# Project_Canary_V4_6.net
KiCad netlist of a schematic drawn in EAGLE
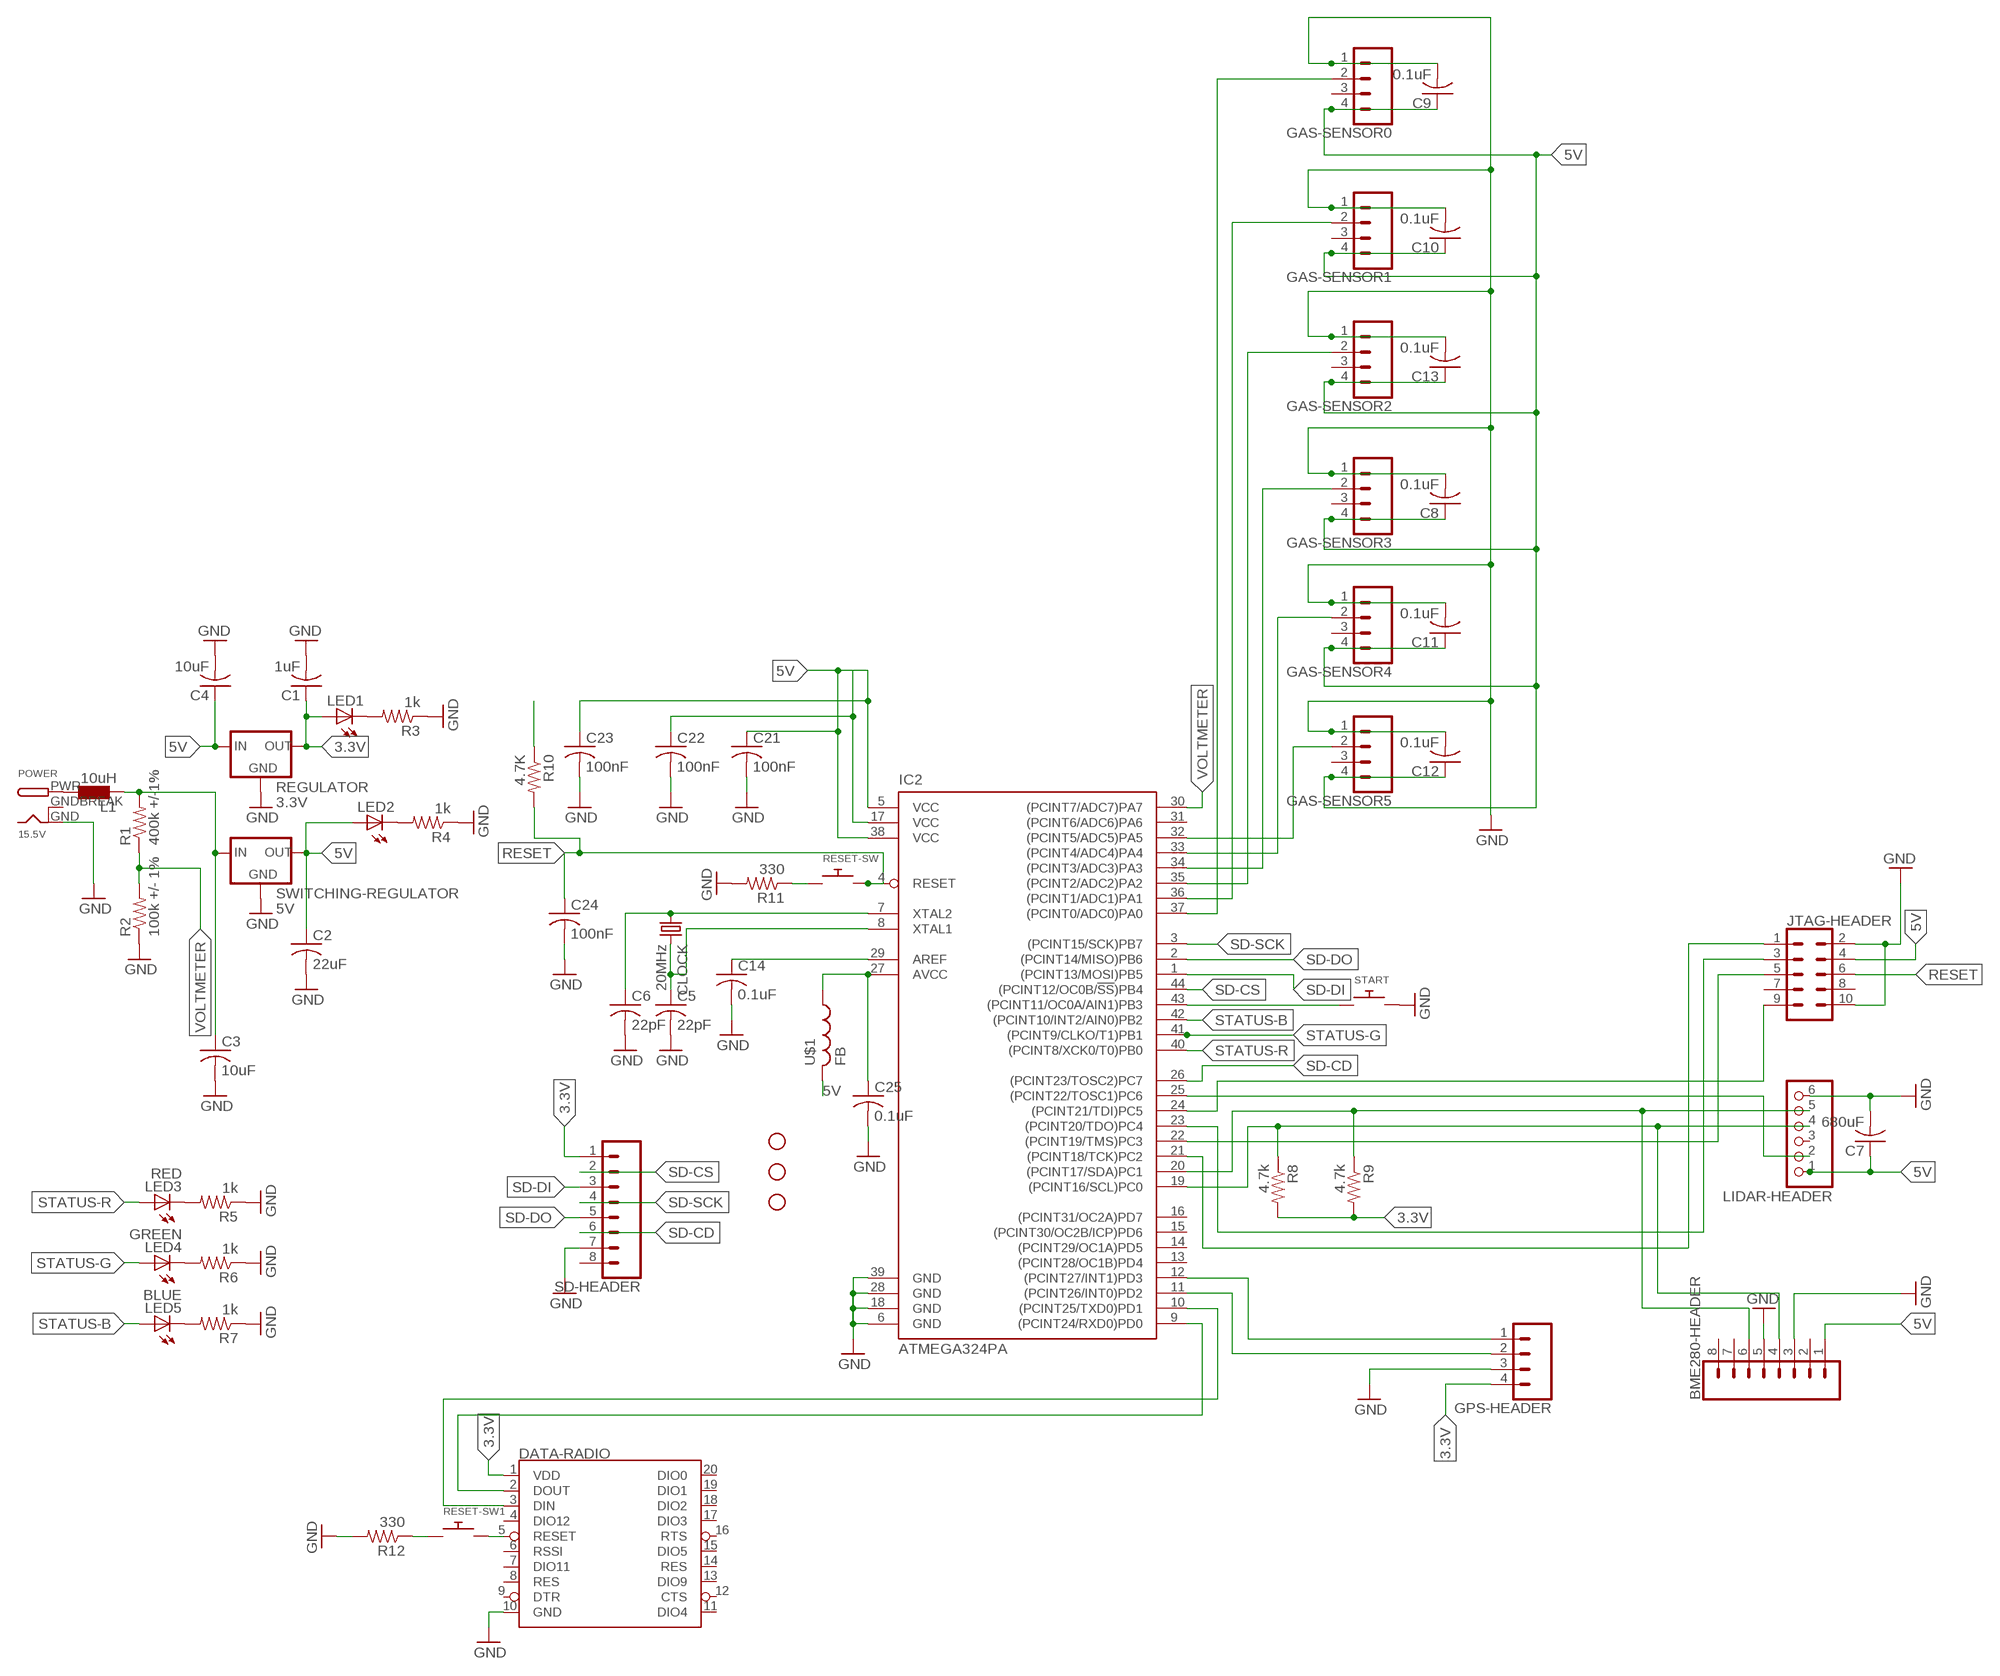
[diagram p0: schematic, sheet 1]

(export (version "E")
  (design (tool "Eeschema 10.0.6"))
  (components
    (comp (ref "BME280-HEADER")
      (value "CONN_08\"")
      (footprint "eagle-import:1X08")
      (libsource (lib "eagle-import") (part "CONN_08{dblquote}"))
    )
    (comp (ref "C1")
      (value "1uF")
      (footprint "eagle-import:C0805")
      (libsource (lib "eagle-import") (part "C-USC0805"))
    )
    (comp (ref "C2")
      (value "22uF")
      (footprint "eagle-import:C0603")
      (libsource (lib "eagle-import") (part "C-USC0603"))
    )
    (comp (ref "C3")
      (value "10uF")
      (footprint "eagle-import:C0805")
      (libsource (lib "eagle-import") (part "C-USC0805"))
    )
    (comp (ref "C4")
      (value "10uF")
      (footprint "eagle-import:C0603")
      (libsource (lib "eagle-import") (part "C-USC0603"))
    )
    (comp (ref "C5")
      (value "22pF")
      (footprint "eagle-import:C0603")
      (libsource (lib "eagle-import") (part "C-USC0603"))
    )
    (comp (ref "C6")
      (value "22pF")
      (footprint "eagle-import:C0603")
      (libsource (lib "eagle-import") (part "C-USC0603"))
    )
    (comp (ref "C7")
      (value "680uF")
      (footprint "eagle-import:C0603")
      (libsource (lib "eagle-import") (part "C-USC0603"))
    )
    (comp (ref "C8")
      (value "0.1uF")
      (footprint "eagle-import:C0603")
      (libsource (lib "eagle-import") (part "C-USC0603"))
    )
    (comp (ref "C9")
      (value "0.1uF")
      (footprint "eagle-import:C0603")
      (libsource (lib "eagle-import") (part "C-USC0603"))
    )
    (comp (ref "C10")
      (value "0.1uF")
      (footprint "eagle-import:C0603")
      (libsource (lib "eagle-import") (part "C-USC0603"))
    )
    (comp (ref "C11")
      (value "0.1uF")
      (footprint "eagle-import:C0603")
      (libsource (lib "eagle-import") (part "C-USC0603"))
    )
    (comp (ref "C12")
      (value "0.1uF")
      (footprint "eagle-import:C0603")
      (libsource (lib "eagle-import") (part "C-USC0603"))
    )
    (comp (ref "C13")
      (value "0.1uF")
      (footprint "eagle-import:C0603")
      (libsource (lib "eagle-import") (part "C-USC0603"))
    )
    (comp (ref "C14")
      (value "0.1uF")
      (footprint "eagle-import:C0603")
      (libsource (lib "eagle-import") (part "C-USC0603"))
    )
    (comp (ref "C21")
      (value "100nF")
      (footprint "eagle-import:C0603")
      (libsource (lib "eagle-import") (part "C-USC0603"))
    )
    (comp (ref "C22")
      (value "100nF")
      (footprint "eagle-import:C0603")
      (libsource (lib "eagle-import") (part "C-USC0603"))
    )
    (comp (ref "C23")
      (value "100nF")
      (footprint "eagle-import:C0603")
      (libsource (lib "eagle-import") (part "C-USC0603"))
    )
    (comp (ref "C24")
      (value "100nF")
      (footprint "eagle-import:C0805")
      (libsource (lib "eagle-import") (part "C-USC0805"))
    )
    (comp (ref "C25")
      (value "0.1uF")
      (footprint "eagle-import:C0603")
      (libsource (lib "eagle-import") (part "C-USC0603"))
    )
    (comp (ref "CLOCK")
      (value "20MHz")
      (footprint "eagle-import:86SMX")
      (libsource (lib "eagle-import") (part "CRYSTAL68SMX"))
    )
    (comp (ref "DATA-RADIO")
      (value "XBEE")
      (footprint "eagle-import:XBEE")
      (libsource (lib "eagle-import") (part "XBEE"))
    )
    (comp (ref "GAS-SENSOR0")
      (value "CONN_04")
      (footprint "eagle-import:1X04")
      (libsource (lib "eagle-import") (part "CONN_04"))
    )
    (comp (ref "GAS-SENSOR1")
      (value "CONN_04")
      (footprint "eagle-import:1X04")
      (libsource (lib "eagle-import") (part "CONN_04"))
    )
    (comp (ref "GAS-SENSOR2")
      (value "CONN_04")
      (footprint "eagle-import:1X04")
      (libsource (lib "eagle-import") (part "CONN_04"))
    )
    (comp (ref "GAS-SENSOR3")
      (value "CONN_04")
      (footprint "eagle-import:1X04")
      (libsource (lib "eagle-import") (part "CONN_04"))
    )
    (comp (ref "GAS-SENSOR4")
      (value "CONN_04")
      (footprint "eagle-import:1X04")
      (libsource (lib "eagle-import") (part "CONN_04"))
    )
    (comp (ref "GAS-SENSOR5")
      (value "CONN_04")
      (footprint "eagle-import:1X04")
      (libsource (lib "eagle-import") (part "CONN_04"))
    )
    (comp (ref "GPS-HEADER")
      (value "CONN_04")
      (footprint "eagle-import:1X04")
      (libsource (lib "eagle-import") (part "CONN_04"))
    )
    (comp (ref "IC2")
      (value "ATMEGA324PA")
      (footprint "eagle-import:TQFP44")
      (fields (field (name "MPN") "ATMEGA644PV-10AU"))
      (libsource (lib "eagle-import") (part "ATMEGA644A"))
    )
    (comp (ref "JTAG-HEADER")
      (value "CONN_05X2PTH")
      (footprint "eagle-import:2X5")
      (libsource (lib "eagle-import") (part "CONN_05X2PTH"))
    )
    (comp (ref "L1")
      (value "10uH")
      (footprint "eagle-import:L1812")
      (libsource (lib "eagle-import") (part "L"))
    )
    (comp (ref "LED1")
      (value "LEDCHIP-LED0805")
      (footprint "eagle-import:CHIP-LED0805")
      (libsource (lib "eagle-import") (part "LEDCHIP-LED0805"))
    )
    (comp (ref "LED2")
      (value "LEDCHIP-LED0805")
      (footprint "eagle-import:CHIP-LED0805")
      (libsource (lib "eagle-import") (part "LEDCHIP-LED0805"))
    )
    (comp (ref "LED3")
      (value "RED")
      (footprint "eagle-import:CHIP-LED0805")
      (libsource (lib "eagle-import") (part "LEDCHIP-LED0805"))
    )
    (comp (ref "LED4")
      (value "GREEN")
      (footprint "eagle-import:CHIP-LED0805")
      (libsource (lib "eagle-import") (part "LEDCHIP-LED0805"))
    )
    (comp (ref "LED5")
      (value "BLUE")
      (footprint "eagle-import:CHIP-LED0805")
      (libsource (lib "eagle-import") (part "LEDCHIP-LED0805"))
    )
    (comp (ref "LIDAR-HEADER")
      (value "PINHD-1X6")
      (footprint "eagle-import:1X06")
      (libsource (lib "eagle-import") (part "PINHD-1X6"))
    )
    (comp (ref "MOUNT-HOLE1")
      (value "STAND-OFF")
      (footprint "eagle-import:STAND-OFF")
      (libsource (lib "eagle-import") (part "STAND-OFF"))
    )
    (comp (ref "MOUNT-HOLE2")
      (value "STAND-OFF")
      (footprint "eagle-import:STAND-OFF")
      (libsource (lib "eagle-import") (part "STAND-OFF"))
    )
    (comp (ref "MOUNT-HOLE3")
      (value "STAND-OFF")
      (footprint "eagle-import:STAND-OFF")
      (libsource (lib "eagle-import") (part "STAND-OFF"))
    )
    (comp (ref "POWER")
      (value "15.5V")
      (footprint "eagle-import:DCJACK_2MM_PTH")
      (libsource (lib "eagle-import") (part "DCBARRELPTH"))
    )
    (comp (ref "R1")
      (value "400k +/-1%")
      (footprint "eagle-import:M0805")
      (libsource (lib "eagle-import") (part "R-US_M0805"))
    )
    (comp (ref "R2")
      (value "100k +/- 1%")
      (footprint "eagle-import:M0805")
      (libsource (lib "eagle-import") (part "R-US_M0805"))
    )
    (comp (ref "R3")
      (value "1k")
      (footprint "eagle-import:M0805")
      (libsource (lib "eagle-import") (part "R-US_M0805"))
    )
    (comp (ref "R4")
      (value "1k")
      (footprint "eagle-import:M0805")
      (libsource (lib "eagle-import") (part "R-US_M0805"))
    )
    (comp (ref "R5")
      (value "1k")
      (footprint "eagle-import:M0805")
      (libsource (lib "eagle-import") (part "R-US_M0805"))
    )
    (comp (ref "R6")
      (value "1k")
      (footprint "eagle-import:M0805")
      (libsource (lib "eagle-import") (part "R-US_M0805"))
    )
    (comp (ref "R7")
      (value "1k")
      (footprint "eagle-import:M0805")
      (libsource (lib "eagle-import") (part "R-US_M0805"))
    )
    (comp (ref "R8")
      (value "4.7k")
      (footprint "eagle-import:M0805")
      (libsource (lib "eagle-import") (part "R-US_M0805"))
    )
    (comp (ref "R9")
      (value "4.7k")
      (footprint "eagle-import:M0805")
      (libsource (lib "eagle-import") (part "R-US_M0805"))
    )
    (comp (ref "R10")
      (value "4.7K")
      (footprint "eagle-import:M0805")
      (libsource (lib "eagle-import") (part "R-US_M0805"))
    )
    (comp (ref "R11")
      (value "330")
      (footprint "eagle-import:M0805")
      (libsource (lib "eagle-import") (part "R-US_M0805"))
    )
    (comp (ref "R12")
      (value "330")
      (footprint "eagle-import:M0805")
      (libsource (lib "eagle-import") (part "R-US_M0805"))
    )
    (comp (ref "REGULATOR")
      (value "3.3V")
      (footprint "eagle-import:TO220-IGO")
      (libsource (lib "eagle-import") (part "V_REG_78XXSINK"))
    )
    (comp (ref "RESET-SW")
      (value "SWITCH_PUSHBUTTONSOFTTOUCHSMD_SJ")
      (footprint "eagle-import:PUSHBUTTON_SMD_SJ")
      (libsource (lib "eagle-import") (part "SWITCH_PUSHBUTTONSOFTTOUCHSMD_SJ"))
    )
    (comp (ref "RESET-SW1")
      (value "SWITCH_PUSHBUTTONSOFTTOUCHSMD_SJ")
      (footprint "eagle-import:PUSHBUTTON_SMD_SJ")
      (libsource (lib "eagle-import") (part "SWITCH_PUSHBUTTONSOFTTOUCHSMD_SJ"))
    )
    (comp (ref "SD-HEADER")
      (value "CONN_08\"")
      (footprint "eagle-import:1X08")
      (libsource (lib "eagle-import") (part "CONN_08{dblquote}"))
    )
    (comp (ref "START")
      (value "SWITCH_PUSHBUTTONSOFTTOUCHSMD_SJ")
      (footprint "eagle-import:PUSHBUTTON_SMD_SJ")
      (libsource (lib "eagle-import") (part "SWITCH_PUSHBUTTONSOFTTOUCHSMD_SJ"))
    )
    (comp (ref "SWITCHING-REGULATOR")
      (value "5V")
      (footprint "eagle-import:TO220-IGO")
      (libsource (lib "eagle-import") (part "V_REG_78XXSINK"))
    )
    (comp (ref "U$1") (value "FB") (footprint "eagle-import:FB") (libsource (lib "eagle-import") (part "FB")))
  )
  (nets
    (net (code "1") (name "/GNDBREAK") (class "Default")
      (node (ref "POWER") (pin "GNDBREAK") (pinfunction "GNDBREAK_GNDBREAK") (pintype "power_in"))
    )
    (net (code "2") (name "3.3V") (class "Default")
      (node (ref "C1") (pin "1") (pinfunction "1_1") (pintype "passive"))
      (node (ref "DATA-RADIO") (pin "1") (pinfunction "VDD_1") (pintype "power_in"))
      (node (ref "GPS-HEADER") (pin "4") (pinfunction "4_4") (pintype "passive"))
      (node (ref "LED1") (pin "A") (pinfunction "A_A") (pintype "passive"))
      (node (ref "R8") (pin "2") (pinfunction "2_2") (pintype "passive"))
      (node (ref "R9") (pin "2") (pinfunction "2_2") (pintype "passive"))
      (node (ref "REGULATOR") (pin "OUT") (pinfunction "OUT_OUT") (pintype "passive"))
      (node (ref "SD-HEADER") (pin "1") (pinfunction "1_1") (pintype "passive"))
    )
    (net (code "3") (name "5V") (class "Default")
      (node (ref "BME280-HEADER") (pin "1") (pinfunction "1_1") (pintype "passive"))
      (node (ref "C10") (pin "1") (pinfunction "1_1") (pintype "passive"))
      (node (ref "C11") (pin "1") (pinfunction "1_1") (pintype "passive"))
      (node (ref "C12") (pin "1") (pinfunction "1_1") (pintype "passive"))
      (node (ref "C13") (pin "1") (pinfunction "1_1") (pintype "passive"))
      (node (ref "C2") (pin "1") (pinfunction "1_1") (pintype "passive"))
      (node (ref "C21") (pin "1") (pinfunction "1_1") (pintype "passive"))
      (node (ref "C22") (pin "1") (pinfunction "1_1") (pintype "passive"))
      (node (ref "C23") (pin "1") (pinfunction "1_1") (pintype "passive"))
      (node (ref "C4") (pin "1") (pinfunction "1_1") (pintype "passive"))
      (node (ref "C7") (pin "1") (pinfunction "1_1") (pintype "passive"))
      (node (ref "C8") (pin "1") (pinfunction "1_1") (pintype "passive"))
      (node (ref "C9") (pin "1") (pinfunction "1_1") (pintype "passive"))
      (node (ref "GAS-SENSOR0") (pin "4") (pinfunction "4_4") (pintype "passive"))
      (node (ref "GAS-SENSOR1") (pin "4") (pinfunction "4_4") (pintype "passive"))
      (node (ref "GAS-SENSOR2") (pin "4") (pinfunction "4_4") (pintype "passive"))
      (node (ref "GAS-SENSOR3") (pin "4") (pinfunction "4_4") (pintype "passive"))
      (node (ref "GAS-SENSOR4") (pin "4") (pinfunction "4_4") (pintype "passive"))
      (node (ref "GAS-SENSOR5") (pin "4") (pinfunction "4_4") (pintype "passive"))
      (node (ref "IC2") (pin "17") (pinfunction "VCC_17") (pintype "power_in"))
      (node (ref "IC2") (pin "38") (pinfunction "VCC_38") (pintype "power_in"))
      (node (ref "IC2") (pin "5") (pinfunction "VCC_5") (pintype "power_in"))
      (node (ref "JTAG-HEADER") (pin "4") (pinfunction "4_4") (pintype "passive"))
      (node (ref "LED2") (pin "A") (pinfunction "A_A") (pintype "passive"))
      (node (ref "LIDAR-HEADER") (pin "1") (pinfunction "1_1") (pintype "passive"))
      (node (ref "REGULATOR") (pin "IN") (pinfunction "IN_IN") (pintype "input"))
      (node (ref "SWITCHING-REGULATOR") (pin "OUT") (pinfunction "OUT_OUT") (pintype "passive"))
      (node (ref "U$1") (pin "P$2") (pinfunction "2_P$2") (pintype "passive"))
    )
    (net (code "4") (name "GND") (class "Default")
      (node (ref "BME280-HEADER") (pin "3") (pinfunction "3_3") (pintype "passive"))
      (node (ref "BME280-HEADER") (pin "5") (pinfunction "5_5") (pintype "passive"))
      (node (ref "C1") (pin "2") (pinfunction "2_2") (pintype "passive"))
      (node (ref "C10") (pin "2") (pinfunction "2_2") (pintype "passive"))
      (node (ref "C11") (pin "2") (pinfunction "2_2") (pintype "passive"))
      (node (ref "C12") (pin "2") (pinfunction "2_2") (pintype "passive"))
      (node (ref "C13") (pin "2") (pinfunction "2_2") (pintype "passive"))
      (node (ref "C14") (pin "2") (pinfunction "2_2") (pintype "passive"))
      (node (ref "C2") (pin "2") (pinfunction "2_2") (pintype "passive"))
      (node (ref "C21") (pin "2") (pinfunction "2_2") (pintype "passive"))
      (node (ref "C22") (pin "2") (pinfunction "2_2") (pintype "passive"))
      (node (ref "C23") (pin "2") (pinfunction "2_2") (pintype "passive"))
      (node (ref "C24") (pin "2") (pinfunction "2_2") (pintype "passive"))
      (node (ref "C25") (pin "2") (pinfunction "2_2") (pintype "passive"))
      (node (ref "C3") (pin "2") (pinfunction "2_2") (pintype "passive"))
      (node (ref "C4") (pin "2") (pinfunction "2_2") (pintype "passive"))
      (node (ref "C5") (pin "2") (pinfunction "2_2") (pintype "passive"))
      (node (ref "C6") (pin "2") (pinfunction "2_2") (pintype "passive"))
      (node (ref "C7") (pin "2") (pinfunction "2_2") (pintype "passive"))
      (node (ref "C8") (pin "2") (pinfunction "2_2") (pintype "passive"))
      (node (ref "C9") (pin "2") (pinfunction "2_2") (pintype "passive"))
      (node (ref "DATA-RADIO") (pin "10") (pinfunction "GND_10") (pintype "power_in"))
      (node (ref "GAS-SENSOR0") (pin "1") (pinfunction "1_1") (pintype "passive"))
      (node (ref "GAS-SENSOR1") (pin "1") (pinfunction "1_1") (pintype "passive"))
      (node (ref "GAS-SENSOR2") (pin "1") (pinfunction "1_1") (pintype "passive"))
      (node (ref "GAS-SENSOR3") (pin "1") (pinfunction "1_1") (pintype "passive"))
      (node (ref "GAS-SENSOR4") (pin "1") (pinfunction "1_1") (pintype "passive"))
      (node (ref "GAS-SENSOR5") (pin "1") (pinfunction "1_1") (pintype "passive"))
      (node (ref "GPS-HEADER") (pin "3") (pinfunction "3_3") (pintype "passive"))
      (node (ref "IC2") (pin "18") (pinfunction "GND_18") (pintype "power_in"))
      (node (ref "IC2") (pin "28") (pinfunction "GND_28") (pintype "power_in"))
      (node (ref "IC2") (pin "39") (pinfunction "GND_39") (pintype "power_in"))
      (node (ref "IC2") (pin "6") (pinfunction "GND_6") (pintype "power_in"))
      (node (ref "JTAG-HEADER") (pin "10") (pinfunction "10_10") (pintype "passive"))
      (node (ref "JTAG-HEADER") (pin "2") (pinfunction "2_2") (pintype "passive"))
      (node (ref "LIDAR-HEADER") (pin "6") (pinfunction "6_6") (pintype "passive"))
      (node (ref "POWER") (pin "GND") (pinfunction "GND_GND") (pintype "power_in"))
      (node (ref "R11") (pin "2") (pinfunction "2_2") (pintype "passive"))
      (node (ref "R12") (pin "2") (pinfunction "2_2") (pintype "passive"))
      (node (ref "R2") (pin "1") (pinfunction "1_1") (pintype "passive"))
      (node (ref "R3") (pin "1") (pinfunction "1_1") (pintype "passive"))
      (node (ref "R4") (pin "1") (pinfunction "1_1") (pintype "passive"))
      (node (ref "R5") (pin "1") (pinfunction "1_1") (pintype "passive"))
      (node (ref "R6") (pin "1") (pinfunction "1_1") (pintype "passive"))
      (node (ref "R7") (pin "1") (pinfunction "1_1") (pintype "passive"))
      (node (ref "REGULATOR") (pin "GND") (pinfunction "GND_GND") (pintype "input"))
      (node (ref "SD-HEADER") (pin "7") (pinfunction "7_7") (pintype "passive"))
      (node (ref "START") (pin "P$2") (pinfunction "P$2_P$2") (pintype "passive"))
      (node (ref "SWITCHING-REGULATOR") (pin "GND") (pinfunction "GND_GND") (pintype "input"))
    )
    (net (code "5") (name "Net-(C3-Pad1)") (class "Default")
      (node (ref "C3") (pin "1") (pinfunction "1_1") (pintype "passive"))
      (node (ref "L1") (pin "2") (pinfunction "2_2") (pintype "passive"))
      (node (ref "R1") (pin "2") (pinfunction "2_2") (pintype "passive"))
      (node (ref "SWITCHING-REGULATOR") (pin "IN") (pinfunction "IN_IN") (pintype "input"))
    )
    (net (code "6") (name "Net-(CLOCK-2)") (class "Default")
      (node (ref "C5") (pin "1") (pinfunction "1_1") (pintype "passive"))
      (node (ref "CLOCK") (pin "4") (pinfunction "2_4") (pintype "passive"))
      (node (ref "IC2") (pin "8") (pinfunction "XTAL1_8") (pintype "bidirectional"))
    )
    (net (code "7") (name "Net-(DATA-RADIO-DIN)") (class "Default")
      (node (ref "DATA-RADIO") (pin "3") (pinfunction "DIN_3") (pintype "input"))
      (node (ref "IC2") (pin "10") (pinfunction "(PCINT25/TXD0)PD1_10") (pintype "bidirectional"))
    )
    (net (code "8") (name "Net-(DATA-RADIO-DOUT)") (class "Default")
      (node (ref "DATA-RADIO") (pin "2") (pinfunction "DOUT_2") (pintype "output"))
      (node (ref "IC2") (pin "9") (pinfunction "(PCINT24/RXD0)PD0_9") (pintype "bidirectional"))
    )
    (net (code "9") (name "Net-(DATA-RADIO-RESET)") (class "Default")
      (node (ref "DATA-RADIO") (pin "5") (pinfunction "RESET_5") (pintype "input"))
      (node (ref "RESET-SW1") (pin "P$2") (pinfunction "P$2_P$2") (pintype "passive"))
    )
    (net (code "10") (name "Net-(IC2-(PCINT0{slash}ADC0)PA0)") (class "Default")
      (node (ref "GAS-SENSOR0") (pin "2") (pinfunction "2_2") (pintype "passive"))
      (node (ref "IC2") (pin "37") (pinfunction "(PCINT0/ADC0)PA0_37") (pintype "bidirectional"))
    )
    (net (code "11") (name "Net-(IC2-(PCINT1{slash}ADC1)PA1)") (class "Default")
      (node (ref "GAS-SENSOR1") (pin "2") (pinfunction "2_2") (pintype "passive"))
      (node (ref "IC2") (pin "36") (pinfunction "(PCINT1/ADC1)PA1_36") (pintype "bidirectional"))
    )
    (net (code "12") (name "Net-(IC2-(PCINT2{slash}ADC2)PA2)") (class "Default")
      (node (ref "GAS-SENSOR2") (pin "2") (pinfunction "2_2") (pintype "passive"))
      (node (ref "IC2") (pin "35") (pinfunction "(PCINT2/ADC2)PA2_35") (pintype "bidirectional"))
    )
    (net (code "13") (name "Net-(IC2-(PCINT3{slash}ADC3)PA3)") (class "Default")
      (node (ref "GAS-SENSOR3") (pin "2") (pinfunction "2_2") (pintype "passive"))
      (node (ref "IC2") (pin "34") (pinfunction "(PCINT3/ADC3)PA3_34") (pintype "bidirectional"))
    )
    (net (code "14") (name "Net-(IC2-(PCINT4{slash}ADC4)PA4)") (class "Default")
      (node (ref "GAS-SENSOR4") (pin "2") (pinfunction "2_2") (pintype "passive"))
      (node (ref "IC2") (pin "33") (pinfunction "(PCINT4/ADC4)PA4_33") (pintype "bidirectional"))
    )
    (net (code "15") (name "Net-(IC2-(PCINT5{slash}ADC5)PA5)") (class "Default")
      (node (ref "GAS-SENSOR5") (pin "2") (pinfunction "2_2") (pintype "passive"))
      (node (ref "IC2") (pin "32") (pinfunction "(PCINT5/ADC5)PA5_32") (pintype "bidirectional"))
    )
    (net (code "16") (name "Net-(IC2-(PCINT11{slash}OC0A{slash}AIN1)PB3)") (class "Default")
      (node (ref "IC2") (pin "43") (pinfunction "(PCINT11/OC0A/AIN1)PB3_43") (pintype "bidirectional"))
      (node (ref "START") (pin "P$1") (pinfunction "P$1_P$1") (pintype "passive"))
    )
    (net (code "17") (name "Net-(IC2-(PCINT16{slash}SCL)PC0)") (class "Default")
      (node (ref "BME280-HEADER") (pin "4") (pinfunction "4_4") (pintype "passive"))
      (node (ref "IC2") (pin "19") (pinfunction "(PCINT16/SCL)PC0_19") (pintype "output"))
      (node (ref "LIDAR-HEADER") (pin "4") (pinfunction "4_4") (pintype "passive"))
      (node (ref "R8") (pin "1") (pinfunction "1_1") (pintype "passive"))
    )
    (net (code "18") (name "Net-(IC2-(PCINT17{slash}SDA)PC1)") (class "Default")
      (node (ref "BME280-HEADER") (pin "6") (pinfunction "6_6") (pintype "passive"))
      (node (ref "IC2") (pin "20") (pinfunction "(PCINT17/SDA)PC1_20") (pintype "output"))
      (node (ref "LIDAR-HEADER") (pin "5") (pinfunction "5_5") (pintype "passive"))
      (node (ref "R9") (pin "1") (pinfunction "1_1") (pintype "passive"))
    )
    (net (code "19") (name "Net-(IC2-(PCINT18{slash}TCK)PC2)") (class "Default")
      (node (ref "IC2") (pin "21") (pinfunction "(PCINT18/TCK)PC2_21") (pintype "output"))
      (node (ref "JTAG-HEADER") (pin "1") (pinfunction "1_1") (pintype "passive"))
    )
    (net (code "20") (name "Net-(IC2-(PCINT19{slash}TMS)PC3)") (class "Default")
      (node (ref "IC2") (pin "22") (pinfunction "(PCINT19/TMS)PC3_22") (pintype "output"))
      (node (ref "JTAG-HEADER") (pin "5") (pinfunction "5_5") (pintype "passive"))
    )
    (net (code "21") (name "Net-(IC2-(PCINT20{slash}TDO)PC4)") (class "Default")
      (node (ref "IC2") (pin "23") (pinfunction "(PCINT20/TDO)PC4_23") (pintype "output"))
      (node (ref "JTAG-HEADER") (pin "3") (pinfunction "3_3") (pintype "passive"))
    )
    (net (code "22") (name "Net-(IC2-(PCINT21{slash}TDI)PC5)") (class "Default")
      (node (ref "IC2") (pin "24") (pinfunction "(PCINT21/TDI)PC5_24") (pintype "output"))
      (node (ref "JTAG-HEADER") (pin "9") (pinfunction "9_9") (pintype "passive"))
    )
    (net (code "23") (name "Net-(IC2-(PCINT22{slash}TOSC1)PC6)") (class "Default")
      (node (ref "IC2") (pin "25") (pinfunction "(PCINT22/TOSC1)PC6_25") (pintype "output"))
      (node (ref "LIDAR-HEADER") (pin "2") (pinfunction "2_2") (pintype "passive"))
    )
    (net (code "24") (name "Net-(IC2-(PCINT26{slash}INT0)PD2)") (class "Default")
      (node (ref "GPS-HEADER") (pin "2") (pinfunction "2_2") (pintype "passive"))
      (node (ref "IC2") (pin "11") (pinfunction "(PCINT26/INT0)PD2_11") (pintype "bidirectional"))
    )
    (net (code "25") (name "Net-(IC2-(PCINT27{slash}INT1)PD3)") (class "Default")
      (node (ref "GPS-HEADER") (pin "1") (pinfunction "1_1") (pintype "passive"))
      (node (ref "IC2") (pin "12") (pinfunction "(PCINT27/INT1)PD3_12") (pintype "bidirectional"))
    )
    (net (code "26") (name "Net-(IC2-AREF)") (class "Default")
      (node (ref "C14") (pin "1") (pinfunction "1_1") (pintype "passive"))
      (node (ref "IC2") (pin "29") (pinfunction "AREF_29") (pintype "passive"))
    )
    (net (code "27") (name "Net-(IC2-AVCC)") (class "Default")
      (node (ref "C25") (pin "1") (pinfunction "1_1") (pintype "passive"))
      (node (ref "IC2") (pin "27") (pinfunction "AVCC_27") (pintype "power_in"))
      (node (ref "U$1") (pin "P$1") (pinfunction "1_P$1") (pintype "passive"))
    )
    (net (code "28") (name "Net-(IC2-XTAL2)") (class "Default")
      (node (ref "C6") (pin "1") (pinfunction "1_1") (pintype "passive"))
      (node (ref "CLOCK") (pin "1") (pinfunction "1_1") (pintype "passive"))
      (node (ref "IC2") (pin "7") (pinfunction "XTAL2_7") (pintype "bidirectional"))
    )
    (net (code "29") (name "Net-(L1-Pad1)") (class "Default")
      (node (ref "L1") (pin "1") (pinfunction "1_1") (pintype "passive"))
      (node (ref "POWER") (pin "PWR") (pinfunction "PWR_PWR") (pintype "power_in"))
    )
    (net (code "30") (name "Net-(LED1-PadC)") (class "Default")
      (node (ref "LED1") (pin "C") (pinfunction "C_C") (pintype "passive"))
      (node (ref "R3") (pin "2") (pinfunction "2_2") (pintype "passive"))
    )
    (net (code "31") (name "Net-(LED2-PadC)") (class "Default")
      (node (ref "LED2") (pin "C") (pinfunction "C_C") (pintype "passive"))
      (node (ref "R4") (pin "2") (pinfunction "2_2") (pintype "passive"))
    )
    (net (code "32") (name "Net-(LED3-PadC)") (class "Default")
      (node (ref "LED3") (pin "C") (pinfunction "C_C") (pintype "passive"))
      (node (ref "R5") (pin "2") (pinfunction "2_2") (pintype "passive"))
    )
    (net (code "33") (name "Net-(LED4-PadC)") (class "Default")
      (node (ref "LED4") (pin "C") (pinfunction "C_C") (pintype "passive"))
      (node (ref "R6") (pin "2") (pinfunction "2_2") (pintype "passive"))
    )
    (net (code "34") (name "Net-(LED5-PadC)") (class "Default")
      (node (ref "LED5") (pin "C") (pinfunction "C_C") (pintype "passive"))
      (node (ref "R7") (pin "2") (pinfunction "2_2") (pintype "passive"))
    )
    (net (code "35") (name "Net-(R11-Pad1)") (class "Default")
      (node (ref "R11") (pin "1") (pinfunction "1_1") (pintype "passive"))
      (node (ref "RESET-SW") (pin "P$1") (pinfunction "P$1_P$1") (pintype "passive"))
    )
    (net (code "36") (name "Net-(R12-Pad1)") (class "Default")
      (node (ref "R12") (pin "1") (pinfunction "1_1") (pintype "passive"))
      (node (ref "RESET-SW1") (pin "P$1") (pinfunction "P$1_P$1") (pintype "passive"))
    )
    (net (code "37") (name "RESET") (class "Default")
      (node (ref "C24") (pin "1") (pinfunction "1_1") (pintype "passive"))
      (node (ref "IC2") (pin "4") (pinfunction "RESET_4") (pintype "input"))
      (node (ref "JTAG-HEADER") (pin "6") (pinfunction "6_6") (pintype "passive"))
      (node (ref "R10") (pin "2") (pinfunction "2_2") (pintype "passive"))
      (node (ref "RESET-SW") (pin "P$2") (pinfunction "P$2_P$2") (pintype "passive"))
    )
    (net (code "38") (name "SD-CD") (class "Default")
      (node (ref "IC2") (pin "26") (pinfunction "(PCINT23/TOSC2)PC7_26") (pintype "output"))
      (node (ref "SD-HEADER") (pin "6") (pinfunction "6_6") (pintype "passive"))
    )
    (net (code "39") (name "SD-CS") (class "Default")
      (node (ref "IC2") (pin "44") (pinfunction "(PCINT12/OC0B/~{SS})PB4_44") (pintype "bidirectional"))
      (node (ref "SD-HEADER") (pin "2") (pinfunction "2_2") (pintype "passive"))
    )
    (net (code "40") (name "SD-DI") (class "Default")
      (node (ref "IC2") (pin "1") (pinfunction "(PCINT13/MOSI)PB5_1") (pintype "bidirectional"))
      (node (ref "SD-HEADER") (pin "3") (pinfunction "3_3") (pintype "passive"))
    )
    (net (code "41") (name "SD-DO") (class "Default")
      (node (ref "IC2") (pin "2") (pinfunction "(PCINT14/MISO)PB6_2") (pintype "bidirectional"))
      (node (ref "SD-HEADER") (pin "5") (pinfunction "5_5") (pintype "passive"))
    )
    (net (code "42") (name "SD-SCK") (class "Default")
      (node (ref "IC2") (pin "3") (pinfunction "(PCINT15/SCK)PB7_3") (pintype "bidirectional"))
      (node (ref "SD-HEADER") (pin "4") (pinfunction "4_4") (pintype "passive"))
    )
    (net (code "43") (name "STATUS-B") (class "Default")
      (node (ref "IC2") (pin "42") (pinfunction "(PCINT10/INT2/AIN0)PB2_42") (pintype "bidirectional"))
      (node (ref "LED5") (pin "A") (pinfunction "A_A") (pintype "passive"))
    )
    (net (code "44") (name "STATUS-G") (class "Default")
      (node (ref "IC2") (pin "41") (pinfunction "(PCINT9/CLKO/T1)PB1_41") (pintype "bidirectional"))
      (node (ref "LED4") (pin "A") (pinfunction "A_A") (pintype "passive"))
    )
    (net (code "45") (name "STATUS-R") (class "Default")
      (node (ref "IC2") (pin "40") (pinfunction "(PCINT8/XCK0/T0)PB0_40") (pintype "bidirectional"))
      (node (ref "LED3") (pin "A") (pinfunction "A_A") (pintype "passive"))
    )
    (net (code "46") (name "VOLTMETER") (class "Default")
      (node (ref "IC2") (pin "30") (pinfunction "(PCINT7/ADC7)PA7_30") (pintype "bidirectional"))
      (node (ref "R1") (pin "1") (pinfunction "1_1") (pintype "passive"))
      (node (ref "R2") (pin "2") (pinfunction "2_2") (pintype "passive"))
    )
    (net (code "47") (name "unconnected-(BME280-HEADER-Pad2)") (class "Default")
      (node (ref "BME280-HEADER") (pin "2") (pinfunction "2_2") (pintype "passive"))
    )
    (net (code "48") (name "unconnected-(BME280-HEADER-Pad7)") (class "Default")
      (node (ref "BME280-HEADER") (pin "7") (pinfunction "7_7") (pintype "passive"))
    )
    (net (code "49") (name "unconnected-(BME280-HEADER-Pad8)") (class "Default")
      (node (ref "BME280-HEADER") (pin "8") (pinfunction "8_8") (pintype "passive"))
    )
    (net (code "50") (name "unconnected-(DATA-RADIO-CTS-Pad12)") (class "Default")
      (node (ref "DATA-RADIO") (pin "12") (pinfunction "CTS_12") (pintype "output"))
    )
    (net (code "51") (name "unconnected-(DATA-RADIO-DIO0-Pad20)") (class "Default")
      (node (ref "DATA-RADIO") (pin "20") (pinfunction "DIO0_20") (pintype "bidirectional"))
    )
    (net (code "52") (name "unconnected-(DATA-RADIO-DIO1-Pad19)") (class "Default")
      (node (ref "DATA-RADIO") (pin "19") (pinfunction "DIO1_19") (pintype "bidirectional"))
    )
    (net (code "53") (name "unconnected-(DATA-RADIO-DIO2-Pad18)") (class "Default")
      (node (ref "DATA-RADIO") (pin "18") (pinfunction "DIO2_18") (pintype "bidirectional"))
    )
    (net (code "54") (name "unconnected-(DATA-RADIO-DIO3-Pad17)") (class "Default")
      (node (ref "DATA-RADIO") (pin "17") (pinfunction "DIO3_17") (pintype "bidirectional"))
    )
    (net (code "55") (name "unconnected-(DATA-RADIO-DIO4-Pad11)") (class "Default")
      (node (ref "DATA-RADIO") (pin "11") (pinfunction "DIO4_11") (pintype "bidirectional"))
    )
    (net (code "56") (name "unconnected-(DATA-RADIO-DIO5-Pad15)") (class "Default")
      (node (ref "DATA-RADIO") (pin "15") (pinfunction "DIO5_15") (pintype "bidirectional"))
    )
    (net (code "57") (name "unconnected-(DATA-RADIO-DIO9-Pad13)") (class "Default")
      (node (ref "DATA-RADIO") (pin "13") (pinfunction "DIO9_13") (pintype "bidirectional"))
    )
    (net (code "58") (name "unconnected-(DATA-RADIO-DIO11-Pad7)") (class "Default")
      (node (ref "DATA-RADIO") (pin "7") (pinfunction "DIO11_7") (pintype "bidirectional"))
    )
    (net (code "59") (name "unconnected-(DATA-RADIO-DIO12-Pad4)") (class "Default")
      (node (ref "DATA-RADIO") (pin "4") (pinfunction "DIO12_4") (pintype "bidirectional"))
    )
    (net (code "60") (name "unconnected-(DATA-RADIO-DTR-Pad9)") (class "Default")
      (node (ref "DATA-RADIO") (pin "9") (pinfunction "DTR_9") (pintype "bidirectional"))
    )
    (net (code "61") (name "unconnected-(DATA-RADIO-RES-Pad8)") (class "Default")
      (node (ref "DATA-RADIO") (pin "8") (pinfunction "RES_8") (pintype "bidirectional"))
    )
    (net (code "62") (name "unconnected-(DATA-RADIO-RES-Pad14)") (class "Default")
      (node (ref "DATA-RADIO") (pin "14") (pinfunction "RES_14") (pintype "bidirectional"))
    )
    (net (code "63") (name "unconnected-(DATA-RADIO-RSSI-Pad6)") (class "Default")
      (node (ref "DATA-RADIO") (pin "6") (pinfunction "RSSI_6") (pintype "bidirectional"))
    )
    (net (code "64") (name "unconnected-(DATA-RADIO-RTS-Pad16)") (class "Default")
      (node (ref "DATA-RADIO") (pin "16") (pinfunction "RTS_16") (pintype "input"))
    )
    (net (code "65") (name "unconnected-(GAS-SENSOR0-Pad3)") (class "Default")
      (node (ref "GAS-SENSOR0") (pin "3") (pinfunction "3_3") (pintype "passive"))
    )
    (net (code "66") (name "unconnected-(GAS-SENSOR1-Pad3)") (class "Default")
      (node (ref "GAS-SENSOR1") (pin "3") (pinfunction "3_3") (pintype "passive"))
    )
    (net (code "67") (name "unconnected-(GAS-SENSOR2-Pad3)") (class "Default")
      (node (ref "GAS-SENSOR2") (pin "3") (pinfunction "3_3") (pintype "passive"))
    )
    (net (code "68") (name "unconnected-(GAS-SENSOR3-Pad3)") (class "Default")
      (node (ref "GAS-SENSOR3") (pin "3") (pinfunction "3_3") (pintype "passive"))
    )
    (net (code "69") (name "unconnected-(GAS-SENSOR4-Pad3)") (class "Default")
      (node (ref "GAS-SENSOR4") (pin "3") (pinfunction "3_3") (pintype "passive"))
    )
    (net (code "70") (name "unconnected-(GAS-SENSOR5-Pad3)") (class "Default")
      (node (ref "GAS-SENSOR5") (pin "3") (pinfunction "3_3") (pintype "passive"))
    )
    (net (code "71") (name "unconnected-(IC2-(PCINT6{slash}ADC6)PA6-Pad31)") (class "Default")
      (node (ref "IC2") (pin "31") (pinfunction "(PCINT6/ADC6)PA6_31") (pintype "bidirectional"))
    )
    (net (code "72") (name "unconnected-(IC2-(PCINT28{slash}OC1B)PD4-Pad13)") (class "Default")
      (node (ref "IC2") (pin "13") (pinfunction "(PCINT28/OC1B)PD4_13") (pintype "bidirectional"))
    )
    (net (code "73") (name "unconnected-(IC2-(PCINT29{slash}OC1A)PD5-Pad14)") (class "Default")
      (node (ref "IC2") (pin "14") (pinfunction "(PCINT29/OC1A)PD5_14") (pintype "bidirectional"))
    )
    (net (code "74") (name "unconnected-(IC2-(PCINT30{slash}OC2B{slash}ICP)PD6-Pad15)") (class "Default")
      (node (ref "IC2") (pin "15") (pinfunction "(PCINT30/OC2B/ICP)PD6_15") (pintype "bidirectional"))
    )
    (net (code "75") (name "unconnected-(IC2-(PCINT31{slash}OC2A)PD7-Pad16)") (class "Default")
      (node (ref "IC2") (pin "16") (pinfunction "(PCINT31/OC2A)PD7_16") (pintype "bidirectional"))
    )
    (net (code "76") (name "unconnected-(JTAG-HEADER-Pad7)") (class "Default")
      (node (ref "JTAG-HEADER") (pin "7") (pinfunction "7_7") (pintype "passive"))
    )
    (net (code "77") (name "unconnected-(JTAG-HEADER-Pad8)") (class "Default")
      (node (ref "JTAG-HEADER") (pin "8") (pinfunction "8_8") (pintype "passive"))
    )
    (net (code "78") (name "unconnected-(LIDAR-HEADER-Pad3)") (class "Default")
      (node (ref "LIDAR-HEADER") (pin "3") (pinfunction "3_3") (pintype "passive"))
    )
    (net (code "79") (name "unconnected-(R10-Pad1)") (class "Default")
      (node (ref "R10") (pin "1") (pinfunction "1_1") (pintype "passive"))
    )
    (net (code "80") (name "unconnected-(SD-HEADER-Pad8)") (class "Default")
      (node (ref "SD-HEADER") (pin "8") (pinfunction "8_8") (pintype "passive"))
    )
  )
)
